# counter-defender-esp8266-pir-mk-1_1.net
KiCad netlist of a schematic drawn in EAGLE
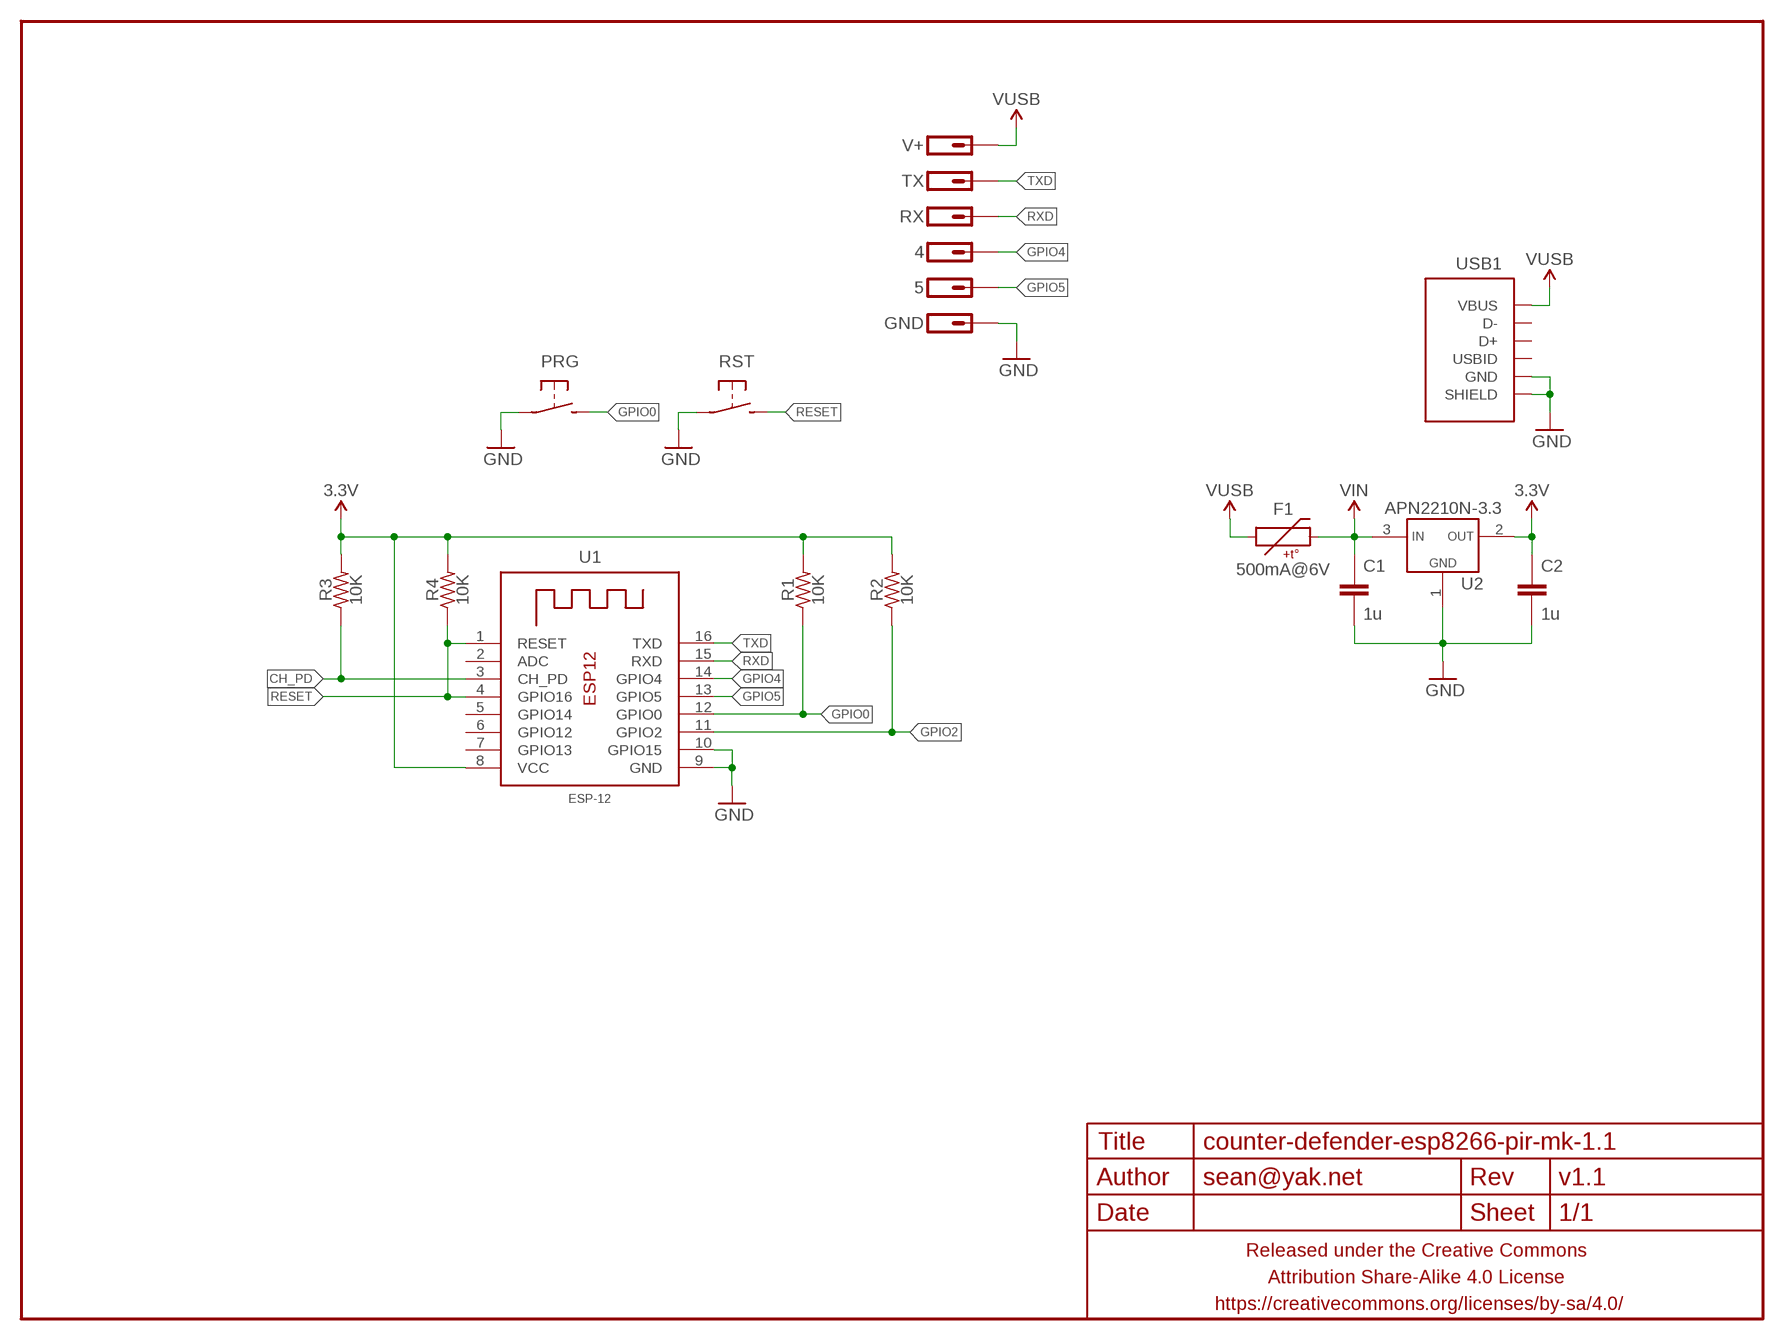
[diagram p0: schematic, sheet 1]

(export (version "E")
  (design (tool "Eeschema 10.0.6"))
  (components
    (comp (ref "4")
      (value "M01PTH")
      (footprint "eagle-import:1X01")
      (libsource (lib "eagle-import") (part "M01PTH"))
    )
    (comp (ref "5")
      (value "M01PTH")
      (footprint "eagle-import:1X01")
      (libsource (lib "eagle-import") (part "M01PTH"))
    )
    (comp (ref "C1")
      (value "1u")
      (footprint "eagle-import:C0603-TIGHTER")
      (libsource (lib "eagle-import") (part "CAPACITOR-CERAMICC0603-TIGHTER"))
    )
    (comp (ref "C2")
      (value "1u")
      (footprint "eagle-import:C0603-TIGHTER")
      (libsource (lib "eagle-import") (part "CAPACITOR-CERAMICC0603-TIGHTER"))
    )
    (comp (ref "F1")
      (value "500mA@6V")
      (footprint "eagle-import:0603")
      (libsource (lib "eagle-import") (part "PTC0603"))
    )
    (comp (ref "FRAME1")
      (value "FRAME-LETTERNO_PACKAGE")
      (footprint "eagle-import:DUMMY")
      (fields (field (name "DESIGNER") "sean@yak.net") (field (name "VERSION") "v1.1"))
      (libsource (lib "eagle-import") (part "FRAME-LETTERNO_PACKAGE"))
    )
    (comp (ref "GND")
      (value "M01PTH")
      (footprint "eagle-import:1X01")
      (libsource (lib "eagle-import") (part "M01PTH"))
    )
    (comp (ref "PRG")
      (value "SPST-NO-TACTSMD-TINIER")
      (footprint "eagle-import:TACTILE_SWITCH_SMD_TINY")
      (libsource (lib "eagle-import") (part "SPST-NO-TACTSMD-TINIER"))
    )
    (comp (ref "R1")
      (value "10K")
      (footprint "eagle-import:R0603-TIGHTER")
      (libsource (lib "eagle-import") (part "RESISTORR0603-TIGHTER"))
    )
    (comp (ref "R2")
      (value "10K")
      (footprint "eagle-import:R0603-TIGHTER")
      (libsource (lib "eagle-import") (part "RESISTORR0603-TIGHTER"))
    )
    (comp (ref "R3")
      (value "10K")
      (footprint "eagle-import:R0603-TIGHTER")
      (libsource (lib "eagle-import") (part "RESISTORR0603-TIGHTER"))
    )
    (comp (ref "R4")
      (value "10K")
      (footprint "eagle-import:R0603-TIGHTER")
      (libsource (lib "eagle-import") (part "RESISTORR0603-TIGHTER"))
    )
    (comp (ref "RST")
      (value "SPST-NO-TACTSMD-TINIER")
      (footprint "eagle-import:TACTILE_SWITCH_SMD_TINY")
      (libsource (lib "eagle-import") (part "SPST-NO-TACTSMD-TINIER"))
    )
    (comp (ref "RX")
      (value "M01PTH")
      (footprint "eagle-import:1X01")
      (libsource (lib "eagle-import") (part "M01PTH"))
    )
    (comp (ref "TX")
      (value "M01PTH")
      (footprint "eagle-import:1X01")
      (libsource (lib "eagle-import") (part "M01PTH"))
    )
    (comp (ref "U1")
      (value "ESP-12")
      (footprint "eagle-import:ESP-12")
      (libsource (lib "eagle-import") (part "ESP-12"))
    )
    (comp (ref "U2")
      (value "APN2210N-3.3")
      (footprint "eagle-import:SOT23")
      (libsource (lib "eagle-import") (part "VREG_1117SOT-23"))
    )
    (comp (ref "USB1")
      (value "USB-AB-SHIELDFCI-10103594-USB-MICRO-B-EVENLESSER")
      (footprint "eagle-import:FCI-10103594-USB-MICRO-B-EVENLESSER")
      (libsource (lib "eagle-import") (part "USB-AB-SHIELDFCI-10103594-USB-MICRO-B-EVENLESSER"))
    )
    (comp (ref "V+")
      (value "M01PTH")
      (footprint "eagle-import:1X01")
      (libsource (lib "eagle-import") (part "M01PTH"))
    )
  )
  (nets
    (net (code "1") (name "3.3V") (class "Default")
      (node (ref "C2") (pin "1") (pinfunction "1_1") (pintype "passive"))
      (node (ref "R1") (pin "2") (pinfunction "2_2") (pintype "passive"))
      (node (ref "R2") (pin "2") (pinfunction "2_2") (pintype "passive"))
      (node (ref "R3") (pin "2") (pinfunction "2_2") (pintype "passive"))
      (node (ref "R4") (pin "2") (pinfunction "2_2") (pintype "passive"))
      (node (ref "U1") (pin "8") (pinfunction "VCC_8") (pintype "power_in"))
      (node (ref "U2") (pin "2") (pinfunction "VOUT_2") (pintype "bidirectional"))
    )
    (net (code "2") (name "CH_PD") (class "Default")
      (node (ref "R3") (pin "1") (pinfunction "1_1") (pintype "passive"))
      (node (ref "U1") (pin "3") (pinfunction "CH_PD_3") (pintype "input"))
    )
    (net (code "3") (name "GND") (class "Default")
      (node (ref "C1") (pin "2") (pinfunction "2_2") (pintype "passive"))
      (node (ref "C2") (pin "2") (pinfunction "2_2") (pintype "passive"))
      (node (ref "GND") (pin "1") (pinfunction "1_1") (pintype "passive"))
      (node (ref "PRG") (pin "P$1") (pinfunction "1_P$1") (pintype "passive"))
      (node (ref "RST") (pin "P$1") (pinfunction "1_P$1") (pintype "passive"))
      (node (ref "U1") (pin "10") (pinfunction "GPIO15_10") (pintype "bidirectional"))
      (node (ref "U1") (pin "9") (pinfunction "GND_9") (pintype "power_in"))
      (node (ref "U2") (pin "1") (pinfunction "GND_1") (pintype "bidirectional"))
      (node (ref "USB1") (pin "5") (pinfunction "GND_5") (pintype "bidirectional"))
      (node (ref "USB1") (pin "SHIELD@1") (pinfunction "SHIELD_SHIELD@1") (pintype "bidirectional"))
      (node (ref "USB1") (pin "SHIELD@2") (pinfunction "SHIELD_SHIELD@2") (pintype "bidirectional"))
      (node (ref "USB1") (pin "SHIELD@3") (pinfunction "SHIELD_SHIELD@3") (pintype "bidirectional"))
      (node (ref "USB1") (pin "SHIELD@4") (pinfunction "SHIELD_SHIELD@4") (pintype "bidirectional"))
      (node (ref "USB1") (pin "SHIELD@5") (pinfunction "SHIELD_SHIELD@5") (pintype "bidirectional"))
      (node (ref "USB1") (pin "SHIELD@6") (pinfunction "SHIELD_SHIELD@6") (pintype "bidirectional"))
    )
    (net (code "4") (name "GPIO0") (class "Default")
      (node (ref "PRG") (pin "P$2") (pinfunction "2_P$2") (pintype "passive"))
      (node (ref "R1") (pin "1") (pinfunction "1_1") (pintype "passive"))
      (node (ref "U1") (pin "12") (pinfunction "GPIO0_12") (pintype "bidirectional"))
    )
    (net (code "5") (name "GPIO2") (class "Default")
      (node (ref "R2") (pin "1") (pinfunction "1_1") (pintype "passive"))
      (node (ref "U1") (pin "11") (pinfunction "GPIO2_11") (pintype "bidirectional"))
    )
    (net (code "6") (name "GPIO4") (class "Default")
      (node (ref "4") (pin "1") (pinfunction "1_1") (pintype "passive"))
      (node (ref "U1") (pin "14") (pinfunction "GPIO4_14") (pintype "bidirectional"))
    )
    (net (code "7") (name "GPIO5") (class "Default")
      (node (ref "5") (pin "1") (pinfunction "1_1") (pintype "passive"))
      (node (ref "U1") (pin "13") (pinfunction "GPIO5_13") (pintype "bidirectional"))
    )
    (net (code "8") (name "RESET") (class "Default")
      (node (ref "R4") (pin "1") (pinfunction "1_1") (pintype "passive"))
      (node (ref "RST") (pin "P$2") (pinfunction "2_P$2") (pintype "passive"))
      (node (ref "U1") (pin "1") (pinfunction "RESET_1") (pintype "input"))
      (node (ref "U1") (pin "4") (pinfunction "GPIO16_4") (pintype "bidirectional"))
    )
    (net (code "9") (name "RXD") (class "Default")
      (node (ref "RX") (pin "1") (pinfunction "1_1") (pintype "passive"))
      (node (ref "U1") (pin "15") (pinfunction "RXD_15") (pintype "input"))
    )
    (net (code "10") (name "TXD") (class "Default")
      (node (ref "TX") (pin "1") (pinfunction "1_1") (pintype "passive"))
      (node (ref "U1") (pin "16") (pinfunction "TXD_16") (pintype "output"))
    )
    (net (code "11") (name "VIN") (class "Default")
      (node (ref "C1") (pin "1") (pinfunction "1_1") (pintype "passive"))
      (node (ref "F1") (pin "2") (pinfunction "2_2") (pintype "passive"))
      (node (ref "U2") (pin "3") (pinfunction "VIN_3") (pintype "bidirectional"))
    )
    (net (code "12") (name "VUSB") (class "Default")
      (node (ref "F1") (pin "1") (pinfunction "1_1") (pintype "passive"))
      (node (ref "USB1") (pin "1") (pinfunction "VBUS_1") (pintype "bidirectional"))
      (node (ref "V+") (pin "1") (pinfunction "1_1") (pintype "passive"))
    )
    (net (code "13") (name "unconnected-(U1-ADC-Pad2)") (class "Default")
      (node (ref "U1") (pin "2") (pinfunction "ADC_2") (pintype "passive"))
    )
    (net (code "14") (name "unconnected-(U1-GPIO12-Pad6)") (class "Default")
      (node (ref "U1") (pin "6") (pinfunction "GPIO12_6") (pintype "bidirectional"))
    )
    (net (code "15") (name "unconnected-(U1-GPIO13-Pad7)") (class "Default")
      (node (ref "U1") (pin "7") (pinfunction "GPIO13_7") (pintype "bidirectional"))
    )
    (net (code "16") (name "unconnected-(U1-GPIO14-Pad5)") (class "Default")
      (node (ref "U1") (pin "5") (pinfunction "GPIO14_5") (pintype "bidirectional"))
    )
    (net (code "17") (name "unconnected-(USB1-D+-Pad3)") (class "Default")
      (node (ref "USB1") (pin "3") (pinfunction "D+_3") (pintype "bidirectional"))
    )
    (net (code "18") (name "unconnected-(USB1-D--Pad2)") (class "Default")
      (node (ref "USB1") (pin "2") (pinfunction "D-_2") (pintype "bidirectional"))
    )
    (net (code "19") (name "unconnected-(USB1-USBID-Pad4)") (class "Default")
      (node (ref "USB1") (pin "4") (pinfunction "USBID_4") (pintype "bidirectional"))
    )
  )
)
